# MCU036A_eZFET_1_4.net
KiCad netlist of a schematic drawn in Altium Designer
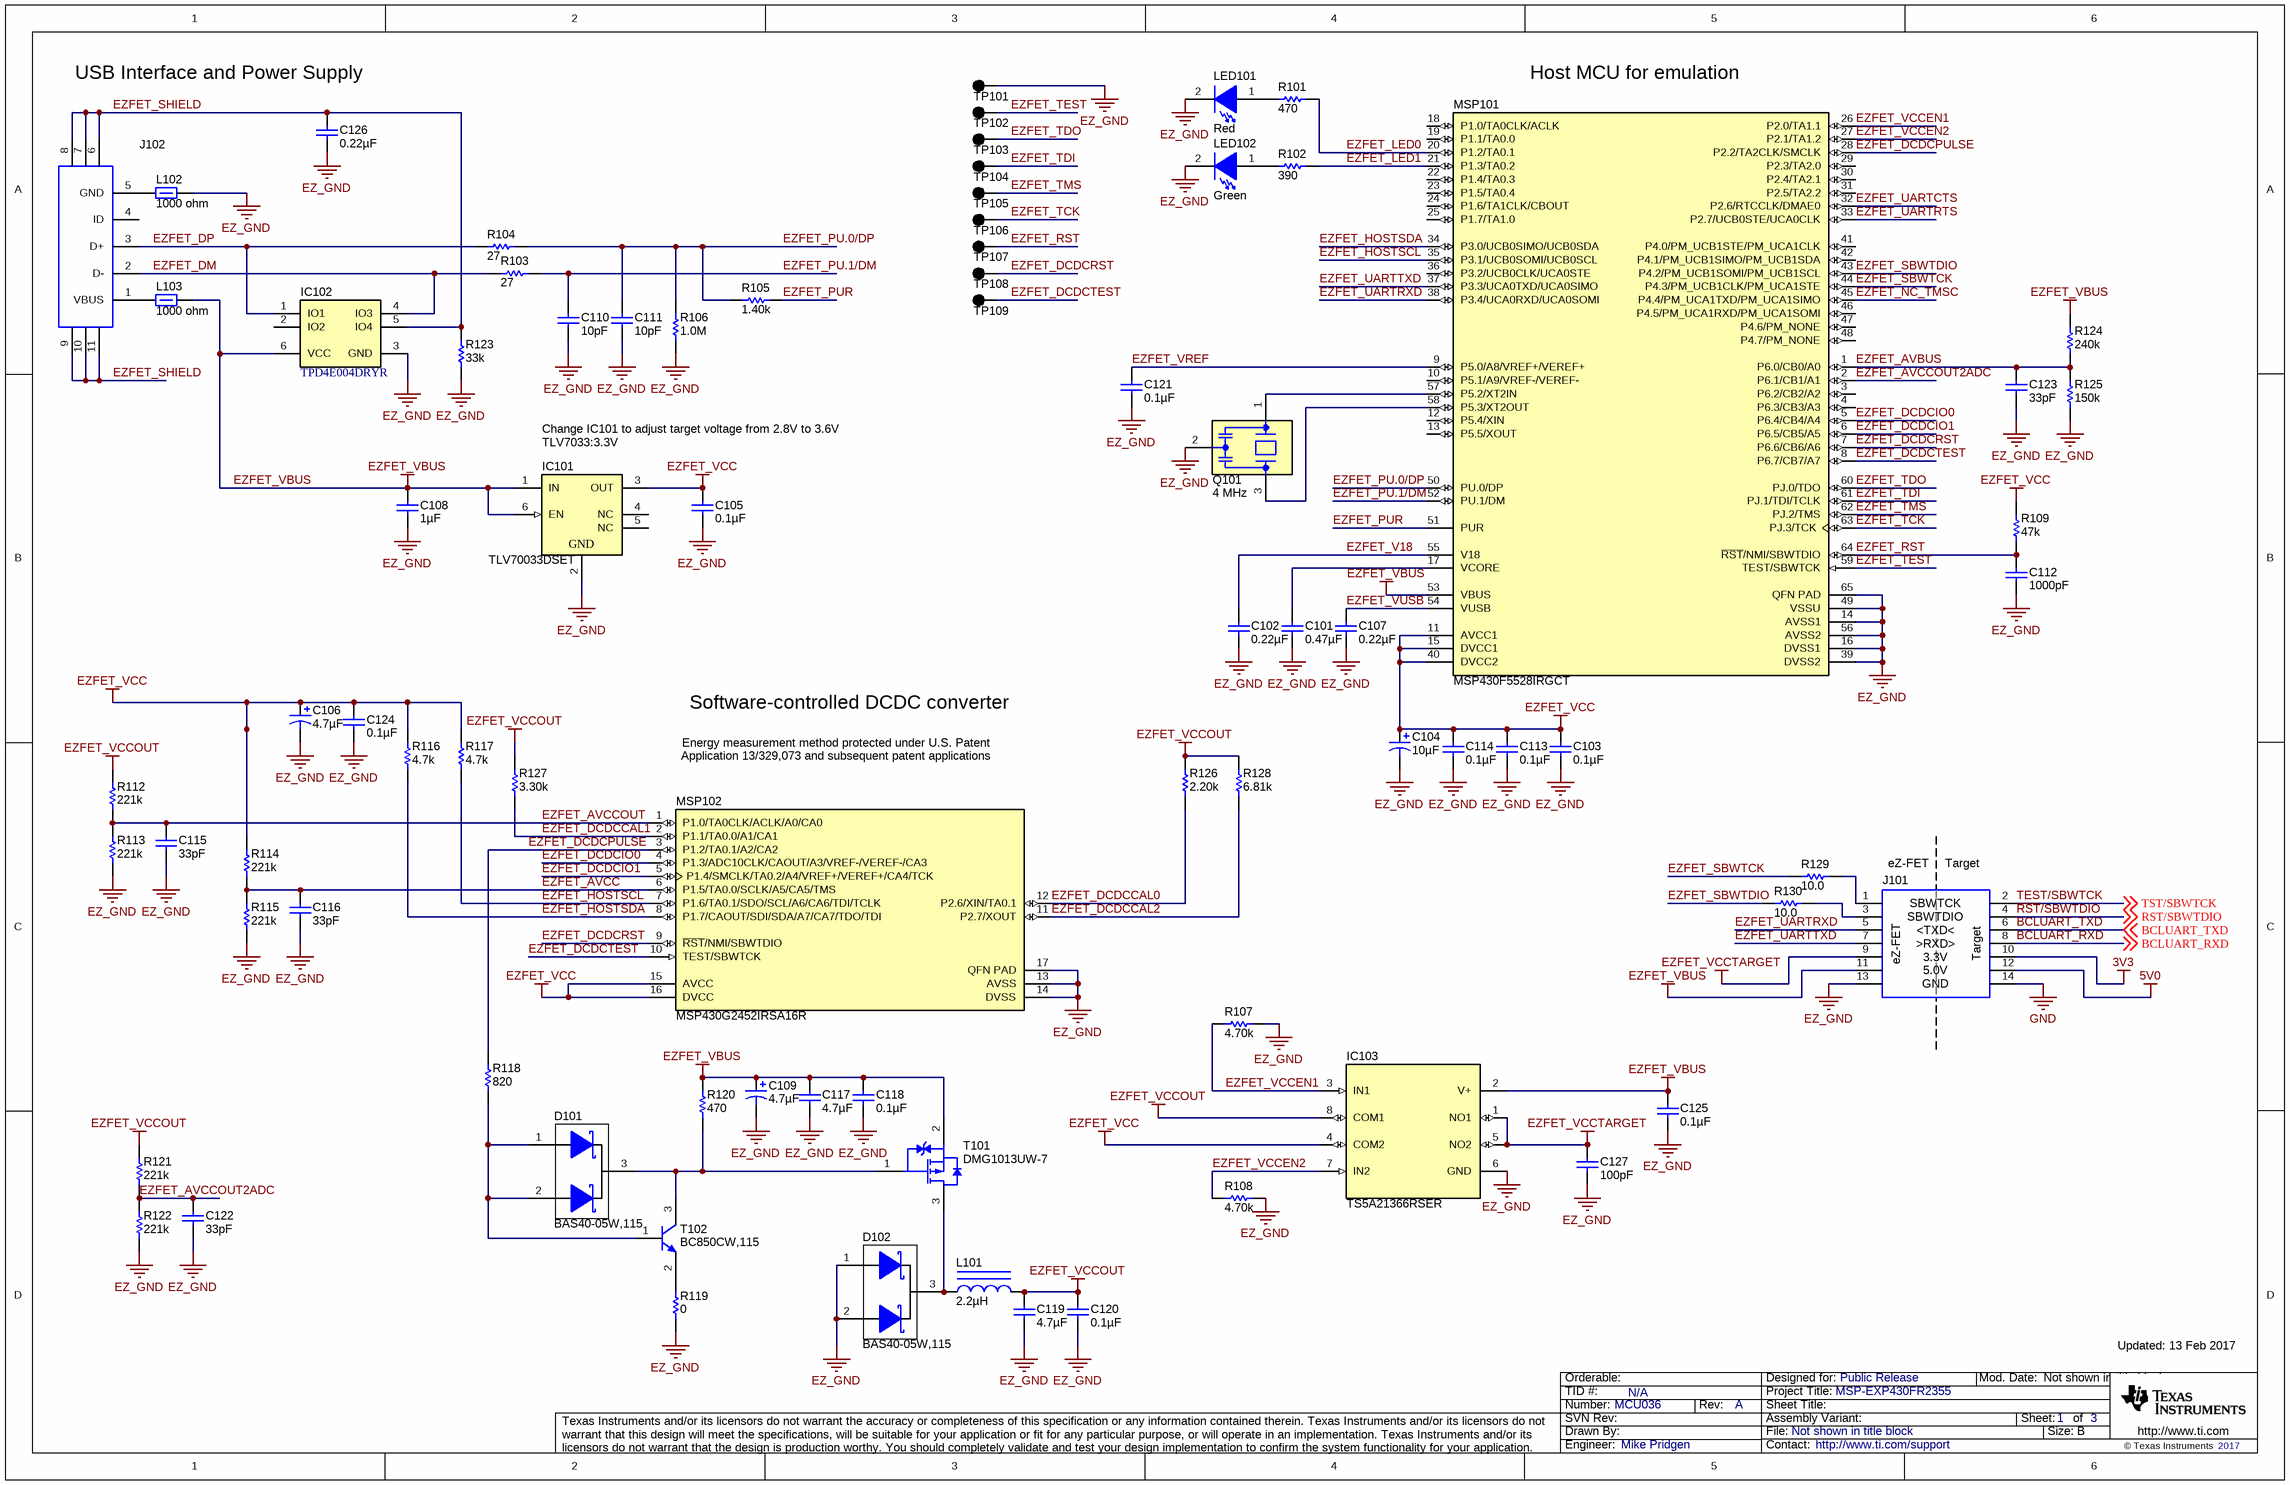
[diagram p0: MCU036A_eZFET_1.4.SchDoc]

(export (version "E")
  (design (tool "Eeschema 10.0.6"))
  (components
    (comp (ref "C101")
      (value "GRM155R61C474KE01")
      (footprint "0402")
      (description "CAP, CERM, 0.47 µF, 16 V, +/- 10%, X5R, 0402")
      (fields (field (name "VALUEDISPLAYED") "0.47µF") (field (name "MANUFACTURER") "MuRata"))
      (libsource (lib "Capacitor_Ceramic") (part "GRM155R61C474KE01"))
    )
    (comp (ref "C102")
      (value "GRM188R61C224KA88D")
      (footprint "0603")
      (description "CAP, CERM, 0.22 µF, 16 V, +/- 10%, X5R, 0603")
      (fields (field (name "VALUEDISPLAYED") "0.22µF") (field (name "MANUFACTURER") "MuRata"))
      (libsource (lib "Capacitor_Ceramic") (part "GRM188R61C224KA88D"))
    )
    (comp (ref "C103")
      (value "GRM155R61A104KA01D")
      (footprint "0402")
      (description "CAP, CERM, 0.1 µF, 10 V, +/- 10%, X5R, 0402")
      (fields (field (name "VALUEDISPLAYED") "0.1µF") (field (name "MANUFACTURER") "MuRata"))
      (libsource (lib "Capacitor_Ceramic") (part "GRM155R61A104KA01D"))
    )
    (comp (ref "C104")
      (value "293D106X0010A2TE3")
      (footprint "3216-18")
      (description "CAP, TA, 10 µF, 10 V, +/- 20%, 3.4 ohm, SMD")
      (fields (field (name "VALUEDISPLAYED") "10µF") (field (name "MANUFACTURER") "Vishay-Sprague"))
      (libsource (lib "Capacitor_Tantalum") (part "293D106X0010A2TE3"))
    )
    (comp (ref "C105")
      (value "GRM155R61A104KA01D")
      (footprint "0402")
      (description "CAP, CERM, 0.1 µF, 10 V, +/- 10%, X5R, 0402")
      (fields (field (name "VALUEDISPLAYED") "0.1µF") (field (name "MANUFACTURER") "MuRata"))
      (libsource (lib "Capacitor_Ceramic") (part "GRM155R61A104KA01D"))
    )
    (comp (ref "C106")
      (value "293D475X9010A2TE3")
      (footprint "3216-18")
      (description "CAP, TA, 4.7 µF, 10 V, +/- 10%, 5 ohm, SMD")
      (fields (field (name "VALUEDISPLAYED") "4.7µF") (field (name "MANUFACTURER") "Vishay-Sprague"))
      (libsource (lib "Capacitor_Tantalum") (part "293D475X9010A2TE3"))
    )
    (comp (ref "C107")
      (value "GRM188R61C224KA88D")
      (footprint "0603")
      (description "CAP, CERM, 0.22 µF, 16 V, +/- 10%, X5R, 0603")
      (fields (field (name "VALUEDISPLAYED") "0.22µF") (field (name "MANUFACTURER") "MuRata"))
      (libsource (lib "Capacitor_Ceramic") (part "GRM188R61C224KA88D"))
    )
    (comp (ref "C108")
      (value "GRM185R61A105KE36D")
      (footprint "0603")
      (description "CAP, CERM, 1 µF, 10 V, +/- 10%, X5R, 0603")
      (fields (field (name "VALUEDISPLAYED") "1µF") (field (name "MANUFACTURER") "MuRata"))
      (libsource (lib "Capacitor_Ceramic") (part "GRM185R61A105KE36D"))
    )
    (comp (ref "C109")
      (value "293D475X9010A2TE3")
      (footprint "3216-18")
      (description "CAP, TA, 4.7 µF, 10 V, +/- 10%, 5 ohm, SMD")
      (fields (field (name "VALUEDISPLAYED") "4.7µF") (field (name "MANUFACTURER") "Vishay-Sprague"))
      (libsource (lib "Capacitor_Tantalum") (part "293D475X9010A2TE3"))
    )
    (comp (ref "C110")
      (value "GRM1555C1H100JA01D")
      (footprint "0402")
      (description "CAP, CERM, 10 pF, 50 V, +/- 5%, C0G/NP0, 0402")
      (fields (field (name "VALUEDISPLAYED") "10pF") (field (name "MANUFACTURER") "MuRata"))
      (libsource (lib "Capacitor_Ceramic") (part "GRM1555C1H100JA01D"))
    )
    (comp (ref "C111")
      (value "GRM1555C1H100JA01D")
      (footprint "0402")
      (description "CAP, CERM, 10 pF, 50 V, +/- 5%, C0G/NP0, 0402")
      (fields (field (name "VALUEDISPLAYED") "10pF") (field (name "MANUFACTURER") "MuRata"))
      (libsource (lib "Capacitor_Ceramic") (part "GRM1555C1H100JA01D"))
    )
    (comp (ref "C112")
      (value "GRM155R71H102KA01D")
      (footprint "0402")
      (description "CAP, CERM, 1000 pF, 50 V, +/- 10%, X7R, 0402")
      (fields (field (name "VALUEDISPLAYED") "1000pF") (field (name "MANUFACTURER") "MuRata"))
      (libsource (lib "Capacitor_Ceramic") (part "GRM155R71H102KA01D"))
    )
    (comp (ref "C113")
      (value "GRM155R61A104KA01D")
      (footprint "0402")
      (description "CAP, CERM, 0.1 µF, 10 V, +/- 10%, X5R, 0402")
      (fields (field (name "VALUEDISPLAYED") "0.1µF") (field (name "MANUFACTURER") "MuRata"))
      (libsource (lib "Capacitor_Ceramic") (part "GRM155R61A104KA01D"))
    )
    (comp (ref "C114")
      (value "GRM155R61A104KA01D")
      (footprint "0402")
      (description "CAP, CERM, 0.1 µF, 10 V, +/- 10%, X5R, 0402")
      (fields (field (name "VALUEDISPLAYED") "0.1µF") (field (name "MANUFACTURER") "MuRata"))
      (libsource (lib "Capacitor_Ceramic") (part "GRM155R61A104KA01D"))
    )
    (comp (ref "C115")
      (value "GRM1555C1H330JA01D")
      (footprint "0402")
      (description "CAP, CERM, 33 pF, 50 V, +/- 5%, C0G/NP0, 0402")
      (fields (field (name "VALUEDISPLAYED") "33pF") (field (name "MANUFACTURER") "MuRata"))
      (libsource (lib "Capacitor_Ceramic") (part "GRM1555C1H330JA01D"))
    )
    (comp (ref "C116")
      (value "GRM1555C1H330JA01D")
      (footprint "0402")
      (description "CAP, CERM, 33 pF, 50 V, +/- 5%, C0G/NP0, 0402")
      (fields (field (name "VALUEDISPLAYED") "33pF") (field (name "MANUFACTURER") "MuRata"))
      (libsource (lib "Capacitor_Ceramic") (part "GRM1555C1H330JA01D"))
    )
    (comp (ref "C117")
      (value "GRM188R61C475KAAJ")
      (footprint "0603")
      (description "CAP, CERM, 4.7 µF, 16 V, +/- 10%, X5R, 0603")
      (fields (field (name "VALUEDISPLAYED") "4.7µF") (field (name "MANUFACTURER") "MuRata"))
      (libsource (lib "Capacitor_Ceramic") (part "GRM188R61C475KAAJ"))
    )
    (comp (ref "C118")
      (value "GRM155R61A104KA01D")
      (footprint "0402")
      (description "CAP, CERM, 0.1 µF, 10 V, +/- 10%, X5R, 0402")
      (fields (field (name "VALUEDISPLAYED") "0.1µF") (field (name "MANUFACTURER") "MuRata"))
      (libsource (lib "Capacitor_Ceramic") (part "GRM155R61A104KA01D"))
    )
    (comp (ref "C119")
      (value "GRM188R61C475KAAJ")
      (footprint "0603")
      (description "CAP, CERM, 4.7 µF, 16 V, +/- 10%, X5R, 0603")
      (fields (field (name "VALUEDISPLAYED") "4.7µF") (field (name "MANUFACTURER") "MuRata"))
      (libsource (lib "Capacitor_Ceramic") (part "GRM188R61C475KAAJ"))
    )
    (comp (ref "C120")
      (value "GRM155R61A104KA01D")
      (footprint "0402")
      (description "CAP, CERM, 0.1 µF, 10 V, +/- 10%, X5R, 0402")
      (fields (field (name "VALUEDISPLAYED") "0.1µF") (field (name "MANUFACTURER") "MuRata"))
      (libsource (lib "Capacitor_Ceramic") (part "GRM155R61A104KA01D"))
    )
    (comp (ref "C121")
      (value "GRM155R61A104KA01D")
      (footprint "0402")
      (description "CAP, CERM, 0.1 µF, 10 V, +/- 10%, X5R, 0402")
      (fields (field (name "VALUEDISPLAYED") "0.1µF") (field (name "MANUFACTURER") "MuRata"))
      (libsource (lib "Capacitor_Ceramic") (part "GRM155R61A104KA01D"))
    )
    (comp (ref "C122")
      (value "GRM1555C1H330JA01D")
      (footprint "0402")
      (description "CAP, CERM, 33 pF, 50 V, +/- 5%, C0G/NP0, 0402")
      (fields (field (name "VALUEDISPLAYED") "33pF") (field (name "MANUFACTURER") "MuRata"))
      (libsource (lib "Capacitor_Ceramic") (part "GRM1555C1H330JA01D"))
    )
    (comp (ref "C123")
      (value "GRM1555C1H330JA01D")
      (footprint "0402")
      (description "CAP, CERM, 33 pF, 50 V, +/- 5%, C0G/NP0, 0402")
      (fields (field (name "VALUEDISPLAYED") "33pF") (field (name "MANUFACTURER") "MuRata"))
      (libsource (lib "Capacitor_Ceramic") (part "GRM1555C1H330JA01D"))
    )
    (comp (ref "C124")
      (value "GRM155R61A104KA01D")
      (footprint "0402")
      (description "CAP, CERM, 0.1 µF, 10 V, +/- 10%, X5R, 0402")
      (fields (field (name "VALUEDISPLAYED") "0.1µF") (field (name "MANUFACTURER") "MuRata"))
      (libsource (lib "Capacitor_Ceramic") (part "GRM155R61A104KA01D"))
    )
    (comp (ref "C125")
      (value "GRM155R61A104KA01D")
      (footprint "0402")
      (description "CAP, CERM, 0.1 µF, 10 V, +/- 10%, X5R, 0402")
      (fields (field (name "VALUEDISPLAYED") "0.1µF") (field (name "MANUFACTURER") "MuRata"))
      (libsource (lib "Capacitor_Ceramic") (part "GRM155R61A104KA01D"))
    )
    (comp (ref "C126")
      (value "GRM155R61A224KE19D")
      (footprint "0402")
      (description "CAP, CERM, 0.22 µF, 10 V, +/- 10%, X5R, 0402")
      (fields (field (name "VALUEDISPLAYED") "0.22µF") (field (name "MANUFACTURER") "MuRata"))
      (libsource (lib "Capacitor_Ceramic") (part "GRM155R61A224KE19D"))
    )
    (comp (ref "C127")
      (value "GRM1555C1H101JA01D")
      (footprint "0402")
      (description "CAP, CERM, 100 pF, 50 V, +/- 5%, C0G/NP0, 0402")
      (fields (field (name "VALUEDISPLAYED") "100pF") (field (name "MANUFACTURER") "MuRata"))
      (libsource (lib "Capacitor_Ceramic") (part "GRM1555C1H101JA01D"))
    )
    (comp (ref "D101")
      (value "BAS40-05W,115")
      (footprint "SOT-323")
      (description "Diode, Schottky, 40 V, 0.12 A, AEC-Q101, SOT-323")
      (fields (field (name "MANUFACTURER") "NXP Semiconductor"))
      (libsource (lib "Diode") (part "BAS40-05W,115"))
    )
    (comp (ref "D102")
      (value "BAS40-05W,115")
      (footprint "SOT-323")
      (description "Diode, Schottky, 40 V, 0.12 A, AEC-Q101, SOT-323")
      (fields (field (name "MANUFACTURER") "NXP Semiconductor"))
      (libsource (lib "Diode") (part "BAS40-05W,115"))
    )
    (comp (ref "IC101")
      (value "TLV70033DSET")
      (footprint "DSE0006A")
      (fields
        (field (name "MANUFACTURER") "Texas Instruments")
        (field (name "ALTERNATE PARTNUMBER") "Equivalent")
      )
      (libsource (lib "TI Power Management Linear Regulator Single Channel LDO (0-350mA)") (part "TLV70033DSET"))
    )
    (comp (ref "IC102")
      (value "TPD4E004DRYR")
      (footprint "DRY0006A")
      (fields
        (field (name "MANUFACTURER") "Texas Instruments")
        (field (name "ALTERNATE PARTNUMBER") "Equivalent")
      )
      (libsource (lib "TI Interface ESD EMI Protection") (part "TPD4E004DRYR"))
    )
    (comp (ref "IC103")
      (value "TS5A21366RSER")
      (footprint "RSE0008A")
      (description "0.75-Ohm DUAL SPST ANALOG SWITCH WITH 1.8-V COMPATIBLE INPUT LOGIC, RSE0008A (UQFN-8)")
      (fields (field (name "MANUFACTURER") "Texas Instruments"))
      (libsource (lib "TI_Pre_Release1") (part "TS5A21366RSER"))
    )
    (comp (ref "J101")
      (value "PEC07DAAN")
      (footprint "PEC07DAAN_Launchpad_EZ-FET")
      (description "Header, 100mil, 7x2, Tin, TH")
      (fields (field (name "MANUFACTURER") "Sullins Connector Solutions"))
      (libsource (lib "Connectors_Sullins") (part "PEC07DAAN"))
    )
    (comp (ref "J102")
      (value "1051640001")
      (footprint "Molex_1051640001")
      (description "Receptacle, USB 2.0, Micro B, 5 Position, R/A, SMT")
      (fields (field (name "MANUFACTURER") "Molex"))
      (libsource (lib "Connectors_Molex") (part "1051640001"))
    )
    (comp (ref "L101")
      (value "CBC2518T2R2M")
      (footprint "CBC2518")
      (description "Inductor, Wirewound, Ceramic, 2.2 µH, 0.89 A, 0.13 ohm, SMD")
      (fields (field (name "VALUEDISPLAYED") "2.2µH") (field (name "MANUFACTURER") "Taiyo Yuden"))
      (libsource (lib "Inductor_Other") (part "CBC2518T2R2M"))
    )
    (comp (ref "L102")
      (value "BLM18HE102SN1D")
      (footprint "0603")
      (description "Ferrite Bead, 1000 ohm @ 100 MHz, 0.6 A, 0603")
      (fields (field (name "VALUEDISPLAYED") "1000 ohm") (field (name "MANUFACTURER") "MuRata"))
      (libsource (lib "FerriteBead") (part "BLM18HE102SN1D"))
    )
    (comp (ref "L103")
      (value "BLM18HE102SN1D")
      (footprint "0603")
      (description "Ferrite Bead, 1000 ohm @ 100 MHz, 0.6 A, 0603")
      (fields (field (name "VALUEDISPLAYED") "1000 ohm") (field (name "MANUFACTURER") "MuRata"))
      (libsource (lib "FerriteBead") (part "BLM18HE102SN1D"))
    )
    (comp (ref "LED101")
      (value "Red")
      (footprint "LED_LTST-C190_Red")
      (description "LED, Red, SMD")
      (fields (field (name "MANUFACTURER") "Lite-On") (field (name "PARTNUMBER") "LTST-C190CKT"))
      (libsource (lib "LED") (part "LTST-C190CKT"))
    )
    (comp (ref "LED102")
      (value "Green")
      (footprint "LED_LTST-C190")
      (description "LED, Green, SMD")
      (fields (field (name "MANUFACTURER") "Lite-On") (field (name "PARTNUMBER") "LTST-C190GKT"))
      (libsource (lib "LED") (part "LTST-C190GKT"))
    )
    (comp (ref "MSP101")
      (value "MSP430F5528IRGCT")
      (footprint "RGC0064B")
      (fields
        (field (name "ALTERNATE PARTNUMBER") "Equivalent")
        (field (name "MANUFACTURER") "Texas Instruments")
      )
      (libsource (lib "TI MCU MSP430") (part "MSP430F5528IRGCT"))
    )
    (comp (ref "MSP102")
      (value "MSP430G2452IRSA16R")
      (footprint "RSA0016B")
      (fields
        (field (name "ALTERNATE PARTNUMBER") "Equivalent")
        (field (name "MANUFACTURER") "Texas Instruments")
      )
      (libsource (lib "TI MCU MSP430") (part "MSP430G2452IRSA16R"))
    )
    (comp (ref "Q101")
      (value "CSTCR4M00G15L99-R0")
      (footprint "Murata_CSTCR")
      (description "Resonator, 4MHz, 39pF SMD")
      (fields (field (name "FREQUENCY") "4 MHz") (field (name "MANUFACTURER") "MuRata"))
      (libsource (lib "Oscillators") (part "CSTCR4M00G15L99-R0"))
    )
    (comp (ref "R101")
      (value "CRCW0402470RJNED")
      (footprint "0402")
      (description "RES, 470, 5%, 0.063 W, 0402")
      (fields (field (name "VALUEDISPLAYED") "470") (field (name "MANUFACTURER") "Vishay-Dale"))
      (libsource (lib "Resistor_0402") (part "CRCW0402470RJNED"))
    )
    (comp (ref "R102")
      (value "CRCW0402390RJNED")
      (footprint "0402")
      (description "RES, 390, 5%, 0.063 W, 0402")
      (fields (field (name "VALUEDISPLAYED") "390") (field (name "MANUFACTURER") "Vishay-Dale"))
      (libsource (lib "Resistor_0402") (part "CRCW0402390RJNED"))
    )
    (comp (ref "R103")
      (value "CRCW040227R0JNED")
      (footprint "0402")
      (description "RES, 27, 5%, 0.063 W, 0402")
      (fields (field (name "VALUEDISPLAYED") "27") (field (name "MANUFACTURER") "Vishay-Dale"))
      (libsource (lib "Resistor_0402") (part "CRCW040227R0JNED"))
    )
    (comp (ref "R104")
      (value "CRCW040227R0JNED")
      (footprint "0402")
      (description "RES, 27, 5%, 0.063 W, 0402")
      (fields (field (name "VALUEDISPLAYED") "27") (field (name "MANUFACTURER") "Vishay-Dale"))
      (libsource (lib "Resistor_0402") (part "CRCW040227R0JNED"))
    )
    (comp (ref "R105")
      (value "CRCW04021K40FKED")
      (footprint "0402")
      (description "RES, 1.40 k, 1%, 0.063 W, 0402")
      (fields (field (name "VALUEDISPLAYED") "1.40k") (field (name "MANUFACTURER") "Vishay-Dale"))
      (libsource (lib "Resistor_0402") (part "CRCW04021K40FKED"))
    )
    (comp (ref "R106")
      (value "CRCW04021M00JNED")
      (footprint "0402")
      (description "RES, 1.0 M, 5%, 0.063 W, 0402")
      (fields (field (name "VALUEDISPLAYED") "1.0M") (field (name "MANUFACTURER") "Vishay-Dale"))
      (libsource (lib "Resistor_0402") (part "CRCW04021M00JNED"))
    )
    (comp (ref "R107")
      (value "CRG0402F4K7")
      (footprint "0402")
      (description "RES, 4.70 k, 1%, 0.063 W, 0402")
      (fields (field (name "VALUEDISPLAYED") "4.70k") (field (name "MANUFACTURER") "TE Connectivity"))
      (libsource (lib "Resistor_0402") (part "CRG0402F4K7"))
    )
    (comp (ref "R108")
      (value "CRG0402F4K7")
      (footprint "0402")
      (description "RES, 4.70 k, 1%, 0.063 W, 0402")
      (fields (field (name "VALUEDISPLAYED") "4.70k") (field (name "MANUFACTURER") "TE Connectivity"))
      (libsource (lib "Resistor_0402") (part "CRG0402F4K7"))
    )
    (comp (ref "R109")
      (value "CRCW040247K0JNED")
      (footprint "0402")
      (description "RES, 47 k, 5%, 0.063 W, 0402")
      (fields (field (name "VALUEDISPLAYED") "47k") (field (name "MANUFACTURER") "Vishay-Dale"))
      (libsource (lib "Resistor_0402") (part "CRCW040247K0JNED"))
    )
    (comp (ref "R112")
      (value "CRCW0402221KFKED")
      (footprint "0402")
      (description "RES, 221 k, 1%, 0.063 W, 0402")
      (fields (field (name "VALUEDISPLAYED") "221k") (field (name "MANUFACTURER") "Vishay-Dale"))
      (libsource (lib "Resistor_0402") (part "CRCW0402221KFKED"))
    )
    (comp (ref "R113")
      (value "CRCW0402221KFKED")
      (footprint "0402")
      (description "RES, 221 k, 1%, 0.063 W, 0402")
      (fields (field (name "VALUEDISPLAYED") "221k") (field (name "MANUFACTURER") "Vishay-Dale"))
      (libsource (lib "Resistor_0402") (part "CRCW0402221KFKED"))
    )
    (comp (ref "R114")
      (value "CRCW0402221KFKED")
      (footprint "0402")
      (description "RES, 221 k, 1%, 0.063 W, 0402")
      (fields (field (name "VALUEDISPLAYED") "221k") (field (name "MANUFACTURER") "Vishay-Dale"))
      (libsource (lib "Resistor_0402") (part "CRCW0402221KFKED"))
    )
    (comp (ref "R115")
      (value "CRCW0402221KFKED")
      (footprint "0402")
      (description "RES, 221 k, 1%, 0.063 W, 0402")
      (fields (field (name "VALUEDISPLAYED") "221k") (field (name "MANUFACTURER") "Vishay-Dale"))
      (libsource (lib "Resistor_0402") (part "CRCW0402221KFKED"))
    )
    (comp (ref "R116")
      (value "CRCW04024K70JNED")
      (footprint "0402")
      (description "RES, 4.7 k, 5%, 0.063 W, 0402")
      (fields (field (name "VALUEDISPLAYED") "4.7k") (field (name "MANUFACTURER") "Vishay-Dale"))
      (libsource (lib "Resistor_0402") (part "CRCW04024K70JNED"))
    )
    (comp (ref "R117")
      (value "CRCW04024K70JNED")
      (footprint "0402")
      (description "RES, 4.7 k, 5%, 0.063 W, 0402")
      (fields (field (name "VALUEDISPLAYED") "4.7k") (field (name "MANUFACTURER") "Vishay-Dale"))
      (libsource (lib "Resistor_0402") (part "CRCW04024K70JNED"))
    )
    (comp (ref "R118")
      (value "RC0402FR-07820RL")
      (footprint "0402")
      (description "RES, 820, 1%, 0.063 W, 0402")
      (fields (field (name "VALUEDISPLAYED") "820") (field (name "MANUFACTURER") "Yageo America"))
      (libsource (lib "Resistor_0402") (part "RC0402FR-07820RL"))
    )
    (comp (ref "R119")
      (value "CRCW04020000Z0ED")
      (footprint "0402")
      (description "RES, 0, 5%, 0.063 W, 0402")
      (fields (field (name "VALUEDISPLAYED") "0") (field (name "MANUFACTURER") "Vishay-Dale"))
      (libsource (lib "Resistor_0402") (part "CRCW04020000Z0ED"))
    )
    (comp (ref "R120")
      (value "CRCW0402470RJNED")
      (footprint "0402")
      (description "RES, 470, 5%, 0.063 W, 0402")
      (fields (field (name "VALUEDISPLAYED") "470") (field (name "MANUFACTURER") "Vishay-Dale"))
      (libsource (lib "Resistor_0402") (part "CRCW0402470RJNED"))
    )
    (comp (ref "R121")
      (value "CRCW0402221KFKED")
      (footprint "0402")
      (description "RES, 221 k, 1%, 0.063 W, 0402")
      (fields (field (name "VALUEDISPLAYED") "221k") (field (name "MANUFACTURER") "Vishay-Dale"))
      (libsource (lib "Resistor_0402") (part "CRCW0402221KFKED"))
    )
    (comp (ref "R122")
      (value "CRCW0402221KFKED")
      (footprint "0402")
      (description "RES, 221 k, 1%, 0.063 W, 0402")
      (fields (field (name "VALUEDISPLAYED") "221k") (field (name "MANUFACTURER") "Vishay-Dale"))
      (libsource (lib "Resistor_0402") (part "CRCW0402221KFKED"))
    )
    (comp (ref "R123")
      (value "CRCW040233K0JNED")
      (footprint "0402")
      (description "RES, 33 k, 5%, 0.063 W, 0402")
      (fields (field (name "VALUEDISPLAYED") "33k") (field (name "MANUFACTURER") "Vishay-Dale"))
      (libsource (lib "Resistor_0402") (part "CRCW040233K0JNED"))
    )
    (comp (ref "R124")
      (value "CRCW0402240KFKED")
      (footprint "0402")
      (description "RES, 240 k, 1%, 0.063 W, 0402")
      (fields (field (name "VALUEDISPLAYED") "240k") (field (name "MANUFACTURER") "Vishay-Dale"))
      (libsource (lib "Resistor_0402") (part "CRCW0402240KFKED"))
    )
    (comp (ref "R125")
      (value "CRCW0402150KFKED")
      (footprint "0402")
      (description "RES, 150 k, 1%, 0.063 W, 0402")
      (fields (field (name "VALUEDISPLAYED") "150k") (field (name "MANUFACTURER") "Vishay-Dale"))
      (libsource (lib "Resistor_0402") (part "CRCW0402150KFKED"))
    )
    (comp (ref "R126")
      (value "CRCW04022K20FKED")
      (footprint "0402")
      (description "RES, 2.20 k, 1%, 0.063 W, 0402")
      (fields (field (name "VALUEDISPLAYED") "2.20k") (field (name "MANUFACTURER") "Vishay-Dale"))
      (libsource (lib "Resistor_0402") (part "CRCW04022K20FKED"))
    )
    (comp (ref "R127")
      (value "ERJ-2RKF3301X")
      (footprint "0402")
      (description "RES, 3.30 k, 1%, 0.1 W, AEC-Q200 Grade 0, 0402")
      (fields (field (name "VALUEDISPLAYED") "3.30k") (field (name "MANUFACTURER") "Panasonic"))
      (libsource (lib "Resistor_0402") (part "ERJ-2RKF3301X"))
    )
    (comp (ref "R128")
      (value "CRCW04026K81FKED")
      (footprint "0402")
      (description "RES, 6.81 k, 1%, 0.063 W, 0402")
      (fields (field (name "VALUEDISPLAYED") "6.81k") (field (name "MANUFACTURER") "Vishay-Dale"))
      (libsource (lib "Resistor_0402") (part "CRCW04026K81FKED"))
    )
    (comp (ref "R129")
      (value "CRCW040210R0FKED")
      (footprint "0402")
      (description "RES, 10.0, 1%, 0.063 W, 0402")
      (fields (field (name "VALUEDISPLAYED") "10.0") (field (name "MANUFACTURER") "Vishay-Dale"))
      (libsource (lib "Resistor_0402") (part "CRCW040210R0FKED"))
    )
    (comp (ref "R130")
      (value "CRCW040210R0FKED")
      (footprint "0402")
      (description "RES, 10.0, 1%, 0.063 W, 0402")
      (fields (field (name "VALUEDISPLAYED") "10.0") (field (name "MANUFACTURER") "Vishay-Dale"))
      (libsource (lib "Resistor_0402") (part "CRCW040210R0FKED"))
    )
    (comp (ref "T101")
      (value "DMG1013UW-7")
      (footprint "SOT-323")
      (description "MOSFET, P-CH, -20 V, -0.82 A, SOT-323")
      (fields (field (name "MANUFACTURER") "Diodes Inc."))
      (libsource (lib "FETs") (part "DMG1013UW-7"))
    )
    (comp (ref "T102")
      (value "BC850CW,115")
      (footprint "SOT-323")
      (description "Transistor, NPN, 45 V, 0.1 A, SOT-323")
      (fields (field (name "MANUFACTURER") "NXP Semiconductor"))
      (libsource (lib "Bipolar_Transistor") (part "BC850CW,115, NXP Semiconductor"))
    )
    (comp (ref "TP101")
      (value "5001")
      (footprint "Keystone5001")
      (description "Test Point, Miniature, Black, TH")
      (fields (field (name "MANUFACTURER") "Keystone"))
      (libsource (lib "Connectors_Keystone") (part "5001"))
    )
    (comp (ref "TP102")
      (value "5001")
      (footprint "Keystone5001")
      (description "Test Point, Miniature, Black, TH")
      (fields (field (name "MANUFACTURER") "Keystone"))
      (libsource (lib "Connectors_Keystone") (part "5001"))
    )
    (comp (ref "TP103")
      (value "5001")
      (footprint "Keystone5001")
      (description "Test Point, Miniature, Black, TH")
      (fields (field (name "MANUFACTURER") "Keystone"))
      (libsource (lib "Connectors_Keystone") (part "5001"))
    )
    (comp (ref "TP104")
      (value "5001")
      (footprint "Keystone5001")
      (description "Test Point, Miniature, Black, TH")
      (fields (field (name "MANUFACTURER") "Keystone"))
      (libsource (lib "Connectors_Keystone") (part "5001"))
    )
    (comp (ref "TP105")
      (value "5001")
      (footprint "Keystone5001")
      (description "Test Point, Miniature, Black, TH")
      (fields (field (name "MANUFACTURER") "Keystone"))
      (libsource (lib "Connectors_Keystone") (part "5001"))
    )
    (comp (ref "TP106")
      (value "5001")
      (footprint "Keystone5001")
      (description "Test Point, Miniature, Black, TH")
      (fields (field (name "MANUFACTURER") "Keystone"))
      (libsource (lib "Connectors_Keystone") (part "5001"))
    )
    (comp (ref "TP107")
      (value "5001")
      (footprint "Keystone5001")
      (description "Test Point, Miniature, Black, TH")
      (fields (field (name "MANUFACTURER") "Keystone"))
      (libsource (lib "Connectors_Keystone") (part "5001"))
    )
    (comp (ref "TP108")
      (value "5001")
      (footprint "Keystone5001")
      (description "Test Point, Miniature, Black, TH")
      (fields (field (name "MANUFACTURER") "Keystone"))
      (libsource (lib "Connectors_Keystone") (part "5001"))
    )
    (comp (ref "TP109")
      (value "5001")
      (footprint "Keystone5001")
      (description "Test Point, Miniature, Black, TH")
      (fields (field (name "MANUFACTURER") "Keystone"))
      (libsource (lib "Connectors_Keystone") (part "5001"))
    )
  )
  (nets
    (net (code "1") (name "/EZFET_AVBUS") (class "Default")
      (node (ref "C123") (pin "2") (pinfunction "2_2") (pintype "passive"))
      (node (ref "MSP101") (pin "1") (pinfunction "P6.0/CB0/A0_1") (pintype "bidirectional"))
      (node (ref "R124") (pin "2") (pinfunction "2_2") (pintype "passive"))
      (node (ref "R125") (pin "1") (pinfunction "1_1") (pintype "passive"))
    )
    (net (code "2") (name "/EZFET_AVCC") (class "Default")
      (node (ref "C116") (pin "2") (pinfunction "2_2") (pintype "passive"))
      (node (ref "MSP102") (pin "6") (pinfunction "P1.5/TA0.0/SCLK/A5/CA5/TMS_6") (pintype "bidirectional"))
      (node (ref "R114") (pin "2") (pinfunction "2_2") (pintype "passive"))
      (node (ref "R115") (pin "1") (pinfunction "1_1") (pintype "passive"))
    )
    (net (code "3") (name "/EZFET_AVCCOUT") (class "Default")
      (node (ref "C115") (pin "2") (pinfunction "2_2") (pintype "passive"))
      (node (ref "MSP102") (pin "1") (pinfunction "P1.0/TA0CLK/ACLK/A0/CA0_1") (pintype "bidirectional"))
      (node (ref "R112") (pin "2") (pinfunction "2_2") (pintype "passive"))
      (node (ref "R113") (pin "1") (pinfunction "1_1") (pintype "passive"))
    )
    (net (code "4") (name "/EZFET_AVCCOUT2ADC") (class "Default")
      (node (ref "C122") (pin "2") (pinfunction "2_2") (pintype "passive"))
      (node (ref "MSP101") (pin "2") (pinfunction "P6.1/CB1/A1_2") (pintype "bidirectional"))
      (node (ref "R121") (pin "2") (pinfunction "2_2") (pintype "passive"))
      (node (ref "R122") (pin "1") (pinfunction "1_1") (pintype "passive"))
    )
    (net (code "5") (name "/EZFET_DCDCCAL0") (class "Default")
      (node (ref "MSP102") (pin "12") (pinfunction "P2.6/XIN/TA0.1_12") (pintype "bidirectional"))
      (node (ref "R126") (pin "1") (pinfunction "1_1") (pintype "passive"))
    )
    (net (code "6") (name "/EZFET_DCDCCAL1") (class "Default")
      (node (ref "MSP102") (pin "2") (pinfunction "P1.1/TA0.0/A1/CA1_2") (pintype "bidirectional"))
      (node (ref "R127") (pin "1") (pinfunction "1_1") (pintype "passive"))
    )
    (net (code "7") (name "/EZFET_DCDCCAL2") (class "Default")
      (node (ref "MSP102") (pin "11") (pinfunction "P2.7/XOUT_11") (pintype "bidirectional"))
      (node (ref "R128") (pin "2") (pinfunction "2_2") (pintype "passive"))
    )
    (net (code "8") (name "/EZFET_DCDCIO0") (class "Default")
      (node (ref "MSP101") (pin "5") (pinfunction "P6.4/CB4/A4_5") (pintype "bidirectional"))
      (node (ref "MSP102") (pin "4") (pinfunction "P1.3/ADC10CLK/CAOUT/A3/VREF-/VEREF-/CA3_4") (pintype "bidirectional"))
    )
    (net (code "9") (name "/EZFET_DCDCIO1") (class "Default")
      (node (ref "MSP101") (pin "6") (pinfunction "P6.5/CB5/A5_6") (pintype "bidirectional"))
      (node (ref "MSP102") (pin "5") (pinfunction "P1.4/SMCLK/TA0.2/A4/VREF+/VEREF+/CA4/TCK_5") (pintype "bidirectional"))
    )
    (net (code "10") (name "/EZFET_DCDCPULSE") (class "Default")
      (node (ref "MSP101") (pin "28") (pinfunction "P2.2/TA2CLK/SMCLK_28") (pintype "bidirectional"))
      (node (ref "MSP102") (pin "3") (pinfunction "P1.2/TA0.1/A2/CA2_3") (pintype "bidirectional"))
      (node (ref "R118") (pin "2") (pinfunction "2_2") (pintype "passive"))
    )
    (net (code "11") (name "/EZFET_DCDCRST") (class "Default")
      (node (ref "MSP101") (pin "7") (pinfunction "P6.6/CB6/A6_7") (pintype "bidirectional"))
      (node (ref "MSP102") (pin "9") (pinfunction "~{RST}/NMI/SBWTDIO_9") (pintype "bidirectional"))
      (node (ref "TP108") (pin "1") (pintype "passive"))
    )
    (net (code "12") (name "/EZFET_DCDCTEST") (class "Default")
      (node (ref "MSP101") (pin "8") (pinfunction "P6.7/CB7/A7_8") (pintype "bidirectional"))
      (node (ref "MSP102") (pin "10") (pinfunction "TEST/SBWTCK_10") (pintype "input"))
      (node (ref "TP109") (pin "1") (pintype "passive"))
    )
    (net (code "13") (name "/EZFET_DM") (class "Default")
      (node (ref "IC102") (pin "4") (pinfunction "IO3_4") (pintype "passive"))
      (node (ref "J102") (pin "2") (pinfunction "D-_2") (pintype "passive"))
      (node (ref "R103") (pin "1") (pinfunction "1_1") (pintype "passive"))
    )
    (net (code "14") (name "/EZFET_DP") (class "Default")
      (node (ref "IC102") (pin "1") (pinfunction "IO1_1") (pintype "passive"))
      (node (ref "J102") (pin "3") (pinfunction "D+_3") (pintype "passive"))
      (node (ref "R104") (pin "1") (pinfunction "1_1") (pintype "passive"))
    )
    (net (code "15") (name "/EZFET_HOSTSCL") (class "Default")
      (node (ref "MSP101") (pin "35") (pinfunction "P3.1/UCB0SOMI/UCB0SCL_35") (pintype "bidirectional"))
      (node (ref "MSP102") (pin "7") (pinfunction "P1.6/TA0.1/SDO/SCL/A6/CA6/TDI/TCLK_7") (pintype "bidirectional"))
      (node (ref "R117") (pin "2") (pinfunction "2_2") (pintype "passive"))
    )
    (net (code "16") (name "/EZFET_HOSTSDA") (class "Default")
      (node (ref "MSP101") (pin "34") (pinfunction "P3.0/UCB0SIMO/UCB0SDA_34") (pintype "bidirectional"))
      (node (ref "MSP102") (pin "8") (pinfunction "P1.7/CAOUT/SDI/SDA/A7/CA7/TDO/TDI_8") (pintype "bidirectional"))
      (node (ref "R116") (pin "2") (pinfunction "2_2") (pintype "passive"))
    )
    (net (code "17") (name "/EZFET_LED0") (class "Default")
      (node (ref "MSP101") (pin "20") (pinfunction "P1.2/TA0.1_20") (pintype "bidirectional"))
      (node (ref "R101") (pin "2") (pinfunction "2_2") (pintype "passive"))
    )
    (net (code "18") (name "/EZFET_LED1") (class "Default")
      (node (ref "MSP101") (pin "21") (pinfunction "P1.3/TA0.2_21") (pintype "bidirectional"))
      (node (ref "R102") (pin "2") (pinfunction "2_2") (pintype "passive"))
    )
    (net (code "19") (name "/EZFET_NC_TMSC") (class "Default")
      (node (ref "MSP101") (pin "45") (pinfunction "P4.4/PM_UCA1TXD/PM_UCA1SIMO_45") (pintype "bidirectional"))
    )
    (net (code "20") (name "/EZFET_PU.0{slash}DP") (class "Default")
      (node (ref "C111") (pin "1") (pinfunction "1_1") (pintype "passive"))
      (node (ref "MSP101") (pin "50") (pinfunction "PU.0/DP_50") (pintype "bidirectional"))
      (node (ref "R104") (pin "2") (pinfunction "2_2") (pintype "passive"))
      (node (ref "R105") (pin "2") (pinfunction "2_2") (pintype "passive"))
      (node (ref "R106") (pin "2") (pinfunction "2_2") (pintype "passive"))
    )
    (net (code "21") (name "/EZFET_PU.1{slash}DM") (class "Default")
      (node (ref "C110") (pin "1") (pinfunction "1_1") (pintype "passive"))
      (node (ref "MSP101") (pin "52") (pinfunction "PU.1/DM_52") (pintype "bidirectional"))
      (node (ref "R103") (pin "2") (pinfunction "2_2") (pintype "passive"))
    )
    (net (code "22") (name "/EZFET_PUR") (class "Default")
      (node (ref "MSP101") (pin "51") (pinfunction "PUR_51") (pintype "passive"))
      (node (ref "R105") (pin "1") (pinfunction "1_1") (pintype "passive"))
    )
    (net (code "23") (name "/EZFET_RST") (class "Default")
      (node (ref "C112") (pin "2") (pinfunction "2_2") (pintype "passive"))
      (node (ref "MSP101") (pin "64") (pinfunction "~{RST}/NMI/SBWTDIO_64") (pintype "bidirectional"))
      (node (ref "R109") (pin "2") (pinfunction "2_2") (pintype "passive"))
      (node (ref "TP107") (pin "1") (pintype "passive"))
    )
    (net (code "24") (name "/EZFET_SBWTCK") (class "Default")
      (node (ref "MSP101") (pin "44") (pinfunction "P4.3/PM_UCB1CLK/PM_UCA1STE_44") (pintype "bidirectional"))
      (node (ref "R129") (pin "1") (pinfunction "1_1") (pintype "passive"))
    )
    (net (code "25") (name "/EZFET_SBWTDIO") (class "Default")
      (node (ref "MSP101") (pin "43") (pinfunction "P4.2/PM_UCB1SOMI/PM_UCB1SCL_43") (pintype "bidirectional"))
      (node (ref "R130") (pin "1") (pinfunction "1_1") (pintype "passive"))
    )
    (net (code "26") (name "/EZFET_SHIELD") (class "Default")
      (node (ref "C126") (pin "2") (pinfunction "2_2") (pintype "passive"))
      (node (ref "IC102") (pin "5") (pinfunction "IO4_5") (pintype "passive"))
      (node (ref "J102") (pin "10") (pinfunction "10_10") (pintype "passive"))
      (node (ref "J102") (pin "11") (pinfunction "11_11") (pintype "passive"))
      (node (ref "J102") (pin "6") (pinfunction "6_6") (pintype "passive"))
      (node (ref "J102") (pin "7") (pinfunction "7_7") (pintype "passive"))
      (node (ref "J102") (pin "8") (pinfunction "8_8") (pintype "passive"))
      (node (ref "J102") (pin "9") (pinfunction "9_9") (pintype "passive"))
      (node (ref "R123") (pin "2") (pinfunction "2_2") (pintype "passive"))
    )
    (net (code "27") (name "/EZFET_TCK") (class "Default")
      (node (ref "MSP101") (pin "63") (pinfunction "PJ.3/TCK_63") (pintype "bidirectional"))
      (node (ref "TP106") (pin "1") (pintype "passive"))
    )
    (net (code "28") (name "/EZFET_TDI") (class "Default")
      (node (ref "MSP101") (pin "61") (pinfunction "PJ.1/TDI/TCLK_61") (pintype "bidirectional"))
      (node (ref "TP104") (pin "1") (pintype "passive"))
    )
    (net (code "29") (name "/EZFET_TDO") (class "Default")
      (node (ref "MSP101") (pin "60") (pinfunction "PJ.0/TDO_60") (pintype "bidirectional"))
      (node (ref "TP103") (pin "1") (pintype "passive"))
    )
    (net (code "30") (name "/EZFET_TEST") (class "Default")
      (node (ref "MSP101") (pin "59") (pinfunction "TEST/SBWTCK_59") (pintype "input"))
      (node (ref "TP102") (pin "1") (pintype "passive"))
    )
    (net (code "31") (name "/EZFET_TMS") (class "Default")
      (node (ref "MSP101") (pin "62") (pinfunction "PJ.2/TMS_62") (pintype "bidirectional"))
      (node (ref "TP105") (pin "1") (pintype "passive"))
    )
    (net (code "32") (name "/EZFET_UARTCTS") (class "Default")
      (node (ref "MSP101") (pin "32") (pinfunction "P2.6/RTCCLK/DMAE0_32") (pintype "bidirectional"))
    )
    (net (code "33") (name "/EZFET_UARTRTS") (class "Default")
      (node (ref "MSP101") (pin "33") (pinfunction "P2.7/UCB0STE/UCA0CLK_33") (pintype "bidirectional"))
    )
    (net (code "34") (name "/EZFET_UARTRXD") (class "Default")
      (node (ref "J101") (pin "5") (pinfunction "5_5") (pintype "passive"))
      (node (ref "MSP101") (pin "38") (pinfunction "P3.4/UCA0RXD/UCA0SOMI_38") (pintype "bidirectional"))
    )
    (net (code "35") (name "/EZFET_UARTTXD") (class "Default")
      (node (ref "J101") (pin "7") (pinfunction "7_7") (pintype "passive"))
      (node (ref "MSP101") (pin "37") (pinfunction "P3.3/UCA0TXD/UCA0SIMO_37") (pintype "bidirectional"))
    )
    (net (code "36") (name "/EZFET_V18") (class "Default")
      (node (ref "C102") (pin "2") (pinfunction "2_2") (pintype "passive"))
      (node (ref "MSP101") (pin "55") (pinfunction "V18_55") (pintype "passive"))
    )
    (net (code "37") (name "/EZFET_VCCEN1") (class "Default")
      (node (ref "IC103") (pin "3") (pinfunction "IN1_3") (pintype "input"))
      (node (ref "MSP101") (pin "26") (pinfunction "P2.0/TA1.1_26") (pintype "bidirectional"))
      (node (ref "R107") (pin "2") (pinfunction "2_2") (pintype "passive"))
    )
    (net (code "38") (name "/EZFET_VCCEN2") (class "Default")
      (node (ref "IC103") (pin "7") (pinfunction "IN2_7") (pintype "input"))
      (node (ref "MSP101") (pin "27") (pinfunction "P2.1/TA1.2_27") (pintype "bidirectional"))
      (node (ref "R108") (pin "2") (pinfunction "2_2") (pintype "passive"))
    )
    (net (code "39") (name "/EZFET_VREF") (class "Default")
      (node (ref "C121") (pin "2") (pinfunction "2_2") (pintype "passive"))
      (node (ref "MSP101") (pin "9") (pinfunction "P5.0/A8/VREF+/VEREF+_9") (pintype "bidirectional"))
    )
    (net (code "40") (name "/EZFET_VUSB") (class "Default")
      (node (ref "C107") (pin "2") (pinfunction "2_2") (pintype "passive"))
      (node (ref "MSP101") (pin "54") (pinfunction "VUSB_54") (pintype "power_in"))
    )
    (net (code "41") (name "3V3") (class "Default")
      (node (ref "J101") (pin "10") (pinfunction "10_10") (pintype "passive"))
    )
    (net (code "42") (name "5V0") (class "Default")
      (node (ref "J101") (pin "12") (pinfunction "12_12") (pintype "passive"))
    )
    (net (code "43") (name "BCLUART_RXD") (class "Default")
      (node (ref "J101") (pin "8") (pinfunction "8_8") (pintype "passive"))
    )
    (net (code "44") (name "BCLUART_TXD") (class "Default")
      (node (ref "J101") (pin "6") (pinfunction "6_6") (pintype "passive"))
    )
    (net (code "45") (name "EZFET_VBUS") (class "Default")
      (node (ref "C108") (pin "2") (pinfunction "2_2") (pintype "passive"))
      (node (ref "C109") (pin "1") (pinfunction "+_1") (pintype "passive"))
      (node (ref "C117") (pin "2") (pinfunction "2_2") (pintype "passive"))
      (node (ref "C118") (pin "2") (pinfunction "2_2") (pintype "passive"))
      (node (ref "C125") (pin "2") (pinfunction "2_2") (pintype "passive"))
      (node (ref "IC101") (pin "1") (pinfunction "IN_1") (pintype "power_in"))
      (node (ref "IC101") (pin "6") (pinfunction "EN_6") (pintype "input"))
      (node (ref "IC102") (pin "6") (pinfunction "VCC_6") (pintype "power_in"))
      (node (ref "IC103") (pin "2") (pinfunction "V+_2") (pintype "power_in"))
      (node (ref "J101") (pin "11") (pinfunction "11_11") (pintype "passive"))
      (node (ref "L103") (pin "2") (pinfunction "2_2") (pintype "passive"))
      (node (ref "MSP101") (pin "53") (pinfunction "VBUS_53") (pintype "power_in"))
      (node (ref "R120") (pin "2") (pinfunction "2_2") (pintype "passive"))
      (node (ref "R124") (pin "1") (pinfunction "1_1") (pintype "passive"))
      (node (ref "T101") (pin "2") (pinfunction "S_2") (pintype "passive"))
    )
    (net (code "46") (name "EZFET_VCC") (class "Default")
      (node (ref "C103") (pin "2") (pinfunction "2_2") (pintype "passive"))
      (node (ref "C104") (pin "1") (pinfunction "+_1") (pintype "passive"))
      (node (ref "C105") (pin "2") (pinfunction "2_2") (pintype "passive"))
      (node (ref "C106") (pin "1") (pinfunction "+_1") (pintype "passive"))
      (node (ref "C113") (pin "2") (pinfunction "2_2") (pintype "passive"))
      (node (ref "C114") (pin "2") (pinfunction "2_2") (pintype "passive"))
      (node (ref "C124") (pin "2") (pinfunction "2_2") (pintype "passive"))
      (node (ref "IC101") (pin "3") (pinfunction "OUT_3") (pintype "power_in"))
      (node (ref "IC103") (pin "4") (pinfunction "COM2_4") (pintype "bidirectional"))
      (node (ref "MSP101") (pin "11") (pinfunction "AVCC1_11") (pintype "power_in"))
      (node (ref "MSP101") (pin "15") (pinfunction "DVCC1_15") (pintype "power_in"))
      (node (ref "MSP101") (pin "40") (pinfunction "DVCC2_40") (pintype "power_in"))
      (node (ref "MSP102") (pin "15") (pinfunction "AVCC_15") (pintype "power_in"))
      (node (ref "MSP102") (pin "16") (pinfunction "DVCC_16") (pintype "power_in"))
      (node (ref "R109") (pin "1") (pinfunction "1_1") (pintype "passive"))
      (node (ref "R114") (pin "1") (pinfunction "1_1") (pintype "passive"))
      (node (ref "R116") (pin "1") (pinfunction "1_1") (pintype "passive"))
      (node (ref "R117") (pin "1") (pinfunction "1_1") (pintype "passive"))
    )
    (net (code "47") (name "EZFET_VCCOUT") (class "Default")
      (node (ref "C119") (pin "2") (pinfunction "2_2") (pintype "passive"))
      (node (ref "C120") (pin "2") (pinfunction "2_2") (pintype "passive"))
      (node (ref "IC103") (pin "8") (pinfunction "COM1_8") (pintype "bidirectional"))
      (node (ref "L101") (pin "2") (pinfunction "2_2") (pintype "passive"))
      (node (ref "R112") (pin "1") (pinfunction "1_1") (pintype "passive"))
      (node (ref "R121") (pin "1") (pinfunction "1_1") (pintype "passive"))
      (node (ref "R126") (pin "2") (pinfunction "2_2") (pintype "passive"))
      (node (ref "R127") (pin "2") (pinfunction "2_2") (pintype "passive"))
      (node (ref "R128") (pin "1") (pinfunction "1_1") (pintype "passive"))
    )
    (net (code "48") (name "EZFET_VCCTARGET") (class "Default")
      (node (ref "C127") (pin "1") (pinfunction "1_1") (pintype "passive"))
      (node (ref "IC103") (pin "1") (pinfunction "NO1_1") (pintype "bidirectional"))
      (node (ref "IC103") (pin "5") (pinfunction "NO2_5") (pintype "bidirectional"))
      (node (ref "J101") (pin "9") (pinfunction "9_9") (pintype "passive"))
    )
    (net (code "49") (name "EZ_GND") (class "Default")
      (node (ref "C101") (pin "1") (pinfunction "1_1") (pintype "passive"))
      (node (ref "C102") (pin "1") (pinfunction "1_1") (pintype "passive"))
      (node (ref "C103") (pin "1") (pinfunction "1_1") (pintype "passive"))
      (node (ref "C104") (pin "2") (pinfunction "-_2") (pintype "passive"))
      (node (ref "C105") (pin "1") (pinfunction "1_1") (pintype "passive"))
      (node (ref "C106") (pin "2") (pinfunction "-_2") (pintype "passive"))
      (node (ref "C107") (pin "1") (pinfunction "1_1") (pintype "passive"))
      (node (ref "C108") (pin "1") (pinfunction "1_1") (pintype "passive"))
      (node (ref "C109") (pin "2") (pinfunction "-_2") (pintype "passive"))
      (node (ref "C110") (pin "2") (pinfunction "2_2") (pintype "passive"))
      (node (ref "C111") (pin "2") (pinfunction "2_2") (pintype "passive"))
      (node (ref "C112") (pin "1") (pinfunction "1_1") (pintype "passive"))
      (node (ref "C113") (pin "1") (pinfunction "1_1") (pintype "passive"))
      (node (ref "C114") (pin "1") (pinfunction "1_1") (pintype "passive"))
      (node (ref "C115") (pin "1") (pinfunction "1_1") (pintype "passive"))
      (node (ref "C116") (pin "1") (pinfunction "1_1") (pintype "passive"))
      (node (ref "C117") (pin "1") (pinfunction "1_1") (pintype "passive"))
      (node (ref "C118") (pin "1") (pinfunction "1_1") (pintype "passive"))
      (node (ref "C119") (pin "1") (pinfunction "1_1") (pintype "passive"))
      (node (ref "C120") (pin "1") (pinfunction "1_1") (pintype "passive"))
      (node (ref "C121") (pin "1") (pinfunction "1_1") (pintype "passive"))
      (node (ref "C122") (pin "1") (pinfunction "1_1") (pintype "passive"))
      (node (ref "C123") (pin "1") (pinfunction "1_1") (pintype "passive"))
      (node (ref "C124") (pin "1") (pinfunction "1_1") (pintype "passive"))
      (node (ref "C125") (pin "1") (pinfunction "1_1") (pintype "passive"))
      (node (ref "C126") (pin "1") (pinfunction "1_1") (pintype "passive"))
      (node (ref "C127") (pin "2") (pinfunction "2_2") (pintype "passive"))
      (node (ref "D102") (pin "1") (pinfunction "A_1") (pintype "passive"))
      (node (ref "D102") (pin "2") (pinfunction "A_2") (pintype "passive"))
      (node (ref "IC101") (pin "2") (pinfunction "GND_2") (pintype "power_in"))
      (node (ref "IC102") (pin "3") (pinfunction "GND_3") (pintype "power_in"))
      (node (ref "IC103") (pin "6") (pinfunction "GND_6") (pintype "power_in"))
      (node (ref "J101") (pin "13") (pinfunction "13_13") (pintype "passive"))
      (node (ref "L102") (pin "2") (pinfunction "2_2") (pintype "passive"))
      (node (ref "LED101") (pin "2") (pinfunction "K_2") (pintype "passive"))
      (node (ref "LED102") (pin "2") (pinfunction "K_2") (pintype "passive"))
      (node (ref "MSP101") (pin "14") (pinfunction "AVSS1_14") (pintype "power_in"))
      (node (ref "MSP101") (pin "16") (pinfunction "DVSS1_16") (pintype "power_in"))
      (node (ref "MSP101") (pin "39") (pinfunction "DVSS2_39") (pintype "power_in"))
      (node (ref "MSP101") (pin "49") (pinfunction "VSSU_49") (pintype "power_in"))
      (node (ref "MSP101") (pin "56") (pinfunction "AVSS2_56") (pintype "power_in"))
      (node (ref "MSP101") (pin "65") (pinfunction "QFN_PAD_65") (pintype "power_in"))
      (node (ref "MSP102") (pin "13") (pinfunction "AVSS_13") (pintype "power_in"))
      (node (ref "MSP102") (pin "14") (pinfunction "DVSS_14") (pintype "power_in"))
      (node (ref "MSP102") (pin "17") (pinfunction "QFN_PAD_17") (pintype "power_in"))
      (node (ref "Q101") (pin "2") (pinfunction "GND_2") (pintype "passive"))
      (node (ref "R106") (pin "1") (pinfunction "1_1") (pintype "passive"))
      (node (ref "R107") (pin "1") (pinfunction "1_1") (pintype "passive"))
      (node (ref "R108") (pin "1") (pinfunction "1_1") (pintype "passive"))
      (node (ref "R113") (pin "2") (pinfunction "2_2") (pintype "passive"))
      (node (ref "R115") (pin "2") (pinfunction "2_2") (pintype "passive"))
      (node (ref "R119") (pin "1") (pinfunction "1_1") (pintype "passive"))
      (node (ref "R122") (pin "2") (pinfunction "2_2") (pintype "passive"))
      (node (ref "R123") (pin "1") (pinfunction "1_1") (pintype "passive"))
      (node (ref "R125") (pin "2") (pinfunction "2_2") (pintype "passive"))
      (node (ref "TP101") (pin "1") (pintype "passive"))
    )
    (net (code "50") (name "GND") (class "Default")
      (node (ref "J101") (pin "14") (pinfunction "14_14") (pintype "passive"))
    )
    (net (code "51") (name "Net-(D101-K)") (class "Default")
      (node (ref "D101") (pin "3") (pinfunction "K_3") (pintype "passive"))
      (node (ref "R120") (pin "1") (pinfunction "1_1") (pintype "passive"))
      (node (ref "T101") (pin "1") (pinfunction "G_1") (pintype "passive"))
      (node (ref "T102") (pin "3") (pinfunction "C_3") (pintype "passive"))
    )
    (net (code "52") (name "Net-(D102-K)") (class "Default")
      (node (ref "D102") (pin "3") (pinfunction "K_3") (pintype "passive"))
      (node (ref "L101") (pin "1") (pinfunction "1_1") (pintype "passive"))
      (node (ref "T101") (pin "3") (pinfunction "D_3") (pintype "passive"))
    )
    (net (code "53") (name "Net-(J101-Pad1)") (class "Default")
      (node (ref "J101") (pin "1") (pinfunction "1_1") (pintype "passive"))
      (node (ref "R129") (pin "2") (pinfunction "2_2") (pintype "passive"))
    )
    (net (code "54") (name "Net-(J101-Pad3)") (class "Default")
      (node (ref "J101") (pin "3") (pinfunction "3_3") (pintype "passive"))
      (node (ref "R130") (pin "2") (pinfunction "2_2") (pintype "passive"))
    )
    (net (code "55") (name "Net-(J102-GND)") (class "Default")
      (node (ref "J102") (pin "5") (pinfunction "GND_5") (pintype "passive"))
      (node (ref "L102") (pin "1") (pinfunction "1_1") (pintype "passive"))
    )
    (net (code "56") (name "Net-(J102-VBUS)") (class "Default")
      (node (ref "J102") (pin "1") (pinfunction "VBUS_1") (pintype "passive"))
      (node (ref "L103") (pin "1") (pinfunction "1_1") (pintype "passive"))
    )
    (net (code "57") (name "Net-(LED101-A)") (class "Default")
      (node (ref "LED101") (pin "1") (pinfunction "A_1") (pintype "passive"))
      (node (ref "R101") (pin "1") (pinfunction "1_1") (pintype "passive"))
    )
    (net (code "58") (name "Net-(LED102-A)") (class "Default")
      (node (ref "LED102") (pin "1") (pinfunction "A_1") (pintype "passive"))
      (node (ref "R102") (pin "1") (pinfunction "1_1") (pintype "passive"))
    )
    (net (code "59") (name "Net-(MSP101-P5.2{slash}XT2IN)") (class "Default")
      (node (ref "MSP101") (pin "57") (pinfunction "P5.2/XT2IN_57") (pintype "bidirectional"))
      (node (ref "Q101") (pin "1") (pinfunction "In_1") (pintype "passive"))
    )
    (net (code "60") (name "Net-(MSP101-P5.3{slash}XT2OUT)") (class "Default")
      (node (ref "MSP101") (pin "58") (pinfunction "P5.3/XT2OUT_58") (pintype "bidirectional"))
      (node (ref "Q101") (pin "3") (pinfunction "Out_3") (pintype "passive"))
    )
    (net (code "61") (name "Net-(MSP101-VCORE)") (class "Default")
      (node (ref "C101") (pin "2") (pinfunction "2_2") (pintype "passive"))
      (node (ref "MSP101") (pin "17") (pinfunction "VCORE_17") (pintype "passive"))
    )
    (net (code "62") (name "Net-(T102-B)") (class "Default")
      (node (ref "D101") (pin "1") (pinfunction "A_1") (pintype "passive"))
      (node (ref "D101") (pin "2") (pinfunction "A_2") (pintype "passive"))
      (node (ref "R118") (pin "1") (pinfunction "1_1") (pintype "passive"))
      (node (ref "T102") (pin "1") (pinfunction "B_1") (pintype "passive"))
    )
    (net (code "63") (name "Net-(T102-E)") (class "Default")
      (node (ref "R119") (pin "2") (pinfunction "2_2") (pintype "passive"))
      (node (ref "T102") (pin "2") (pinfunction "E_2") (pintype "passive"))
    )
    (net (code "64") (name "RST{slash}SBWTDIO") (class "Default")
      (node (ref "J101") (pin "4") (pinfunction "4_4") (pintype "passive"))
    )
    (net (code "65") (name "TST{slash}SBWTCK") (class "Default")
      (node (ref "J101") (pin "2") (pinfunction "2_2") (pintype "passive"))
    )
    (net (code "66") (name "unconnected-(IC101-NC-Pad4)") (class "Default")
      (node (ref "IC101") (pin "4") (pinfunction "NC_4") (pintype "passive"))
    )
    (net (code "67") (name "unconnected-(IC101-NC-Pad5)") (class "Default")
      (node (ref "IC101") (pin "5") (pinfunction "NC_5") (pintype "passive"))
    )
    (net (code "68") (name "unconnected-(IC102-IO2-Pad2)") (class "Default")
      (node (ref "IC102") (pin "2") (pinfunction "IO2_2") (pintype "passive"))
    )
    (net (code "69") (name "unconnected-(J102-ID-Pad4)") (class "Default")
      (node (ref "J102") (pin "4") (pinfunction "ID_4") (pintype "passive"))
    )
    (net (code "70") (name "unconnected-(MSP101-P1.0{slash}TA0CLK{slash}ACLK-Pad18)") (class "Default")
      (node (ref "MSP101") (pin "18") (pinfunction "P1.0/TA0CLK/ACLK_18") (pintype "bidirectional"))
    )
    (net (code "71") (name "unconnected-(MSP101-P1.1{slash}TA0.0-Pad19)") (class "Default")
      (node (ref "MSP101") (pin "19") (pinfunction "P1.1/TA0.0_19") (pintype "bidirectional"))
    )
    (net (code "72") (name "unconnected-(MSP101-P1.4{slash}TA0.3-Pad22)") (class "Default")
      (node (ref "MSP101") (pin "22") (pinfunction "P1.4/TA0.3_22") (pintype "bidirectional"))
    )
    (net (code "73") (name "unconnected-(MSP101-P1.5{slash}TA0.4-Pad23)") (class "Default")
      (node (ref "MSP101") (pin "23") (pinfunction "P1.5/TA0.4_23") (pintype "bidirectional"))
    )
    (net (code "74") (name "unconnected-(MSP101-P1.6{slash}TA1CLK{slash}CBOUT-Pad24)") (class "Default")
      (node (ref "MSP101") (pin "24") (pinfunction "P1.6/TA1CLK/CBOUT_24") (pintype "bidirectional"))
    )
    (net (code "75") (name "unconnected-(MSP101-P1.7{slash}TA1.0-Pad25)") (class "Default")
      (node (ref "MSP101") (pin "25") (pinfunction "P1.7/TA1.0_25") (pintype "bidirectional"))
    )
    (net (code "76") (name "unconnected-(MSP101-P2.3{slash}TA2.0-Pad29)") (class "Default")
      (node (ref "MSP101") (pin "29") (pinfunction "P2.3/TA2.0_29") (pintype "bidirectional"))
    )
    (net (code "77") (name "unconnected-(MSP101-P2.4{slash}TA2.1-Pad30)") (class "Default")
      (node (ref "MSP101") (pin "30") (pinfunction "P2.4/TA2.1_30") (pintype "bidirectional"))
    )
    (net (code "78") (name "unconnected-(MSP101-P2.5{slash}TA2.2-Pad31)") (class "Default")
      (node (ref "MSP101") (pin "31") (pinfunction "P2.5/TA2.2_31") (pintype "bidirectional"))
    )
    (net (code "79") (name "unconnected-(MSP101-P3.2{slash}UCB0CLK{slash}UCA0STE-Pad36)") (class "Default")
      (node (ref "MSP101") (pin "36") (pinfunction "P3.2/UCB0CLK/UCA0STE_36") (pintype "bidirectional"))
    )
    (net (code "80") (name "unconnected-(MSP101-P4.0{slash}PM_UCB1STE{slash}PM_UCA1CLK-Pad41)") (class "Default")
      (node (ref "MSP101") (pin "41") (pinfunction "P4.0/PM_UCB1STE/PM_UCA1CLK_41") (pintype "bidirectional"))
    )
    (net (code "81") (name "unconnected-(MSP101-P4.1{slash}PM_UCB1SIMO{slash}PM_UCB1SDA-Pad42)") (class "Default")
      (node (ref "MSP101") (pin "42") (pinfunction "P4.1/PM_UCB1SIMO/PM_UCB1SDA_42") (pintype "bidirectional"))
    )
    (net (code "82") (name "unconnected-(MSP101-P4.5{slash}PM_UCA1RXD{slash}PM_UCA1SOMI-Pad46)") (class "Default")
      (node (ref "MSP101") (pin "46") (pinfunction "P4.5/PM_UCA1RXD/PM_UCA1SOMI_46") (pintype "bidirectional"))
    )
    (net (code "83") (name "unconnected-(MSP101-P4.6{slash}PM_NONE-Pad47)") (class "Default")
      (node (ref "MSP101") (pin "47") (pinfunction "P4.6/PM_NONE_47") (pintype "bidirectional"))
    )
    (net (code "84") (name "unconnected-(MSP101-P4.7{slash}PM_NONE-Pad48)") (class "Default")
      (node (ref "MSP101") (pin "48") (pinfunction "P4.7/PM_NONE_48") (pintype "bidirectional"))
    )
    (net (code "85") (name "unconnected-(MSP101-P5.1{slash}A9{slash}VREF-{slash}VEREF--Pad10)") (class "Default")
      (node (ref "MSP101") (pin "10") (pinfunction "P5.1/A9/VREF-/VEREF-_10") (pintype "bidirectional"))
    )
    (net (code "86") (name "unconnected-(MSP101-P5.4{slash}XIN-Pad12)") (class "Default")
      (node (ref "MSP101") (pin "12") (pinfunction "P5.4/XIN_12") (pintype "bidirectional"))
    )
    (net (code "87") (name "unconnected-(MSP101-P5.5{slash}XOUT-Pad13)") (class "Default")
      (node (ref "MSP101") (pin "13") (pinfunction "P5.5/XOUT_13") (pintype "bidirectional"))
    )
    (net (code "88") (name "unconnected-(MSP101-P6.2{slash}CB2{slash}A2-Pad3)") (class "Default")
      (node (ref "MSP101") (pin "3") (pinfunction "P6.2/CB2/A2_3") (pintype "bidirectional"))
    )
    (net (code "89") (name "unconnected-(MSP101-P6.3{slash}CB3{slash}A3-Pad4)") (class "Default")
      (node (ref "MSP101") (pin "4") (pinfunction "P6.3/CB3/A3_4") (pintype "bidirectional"))
    )
  )
)
